# Task_2021-06-01.net
KiCad netlist of a schematic drawn in EasyEDA
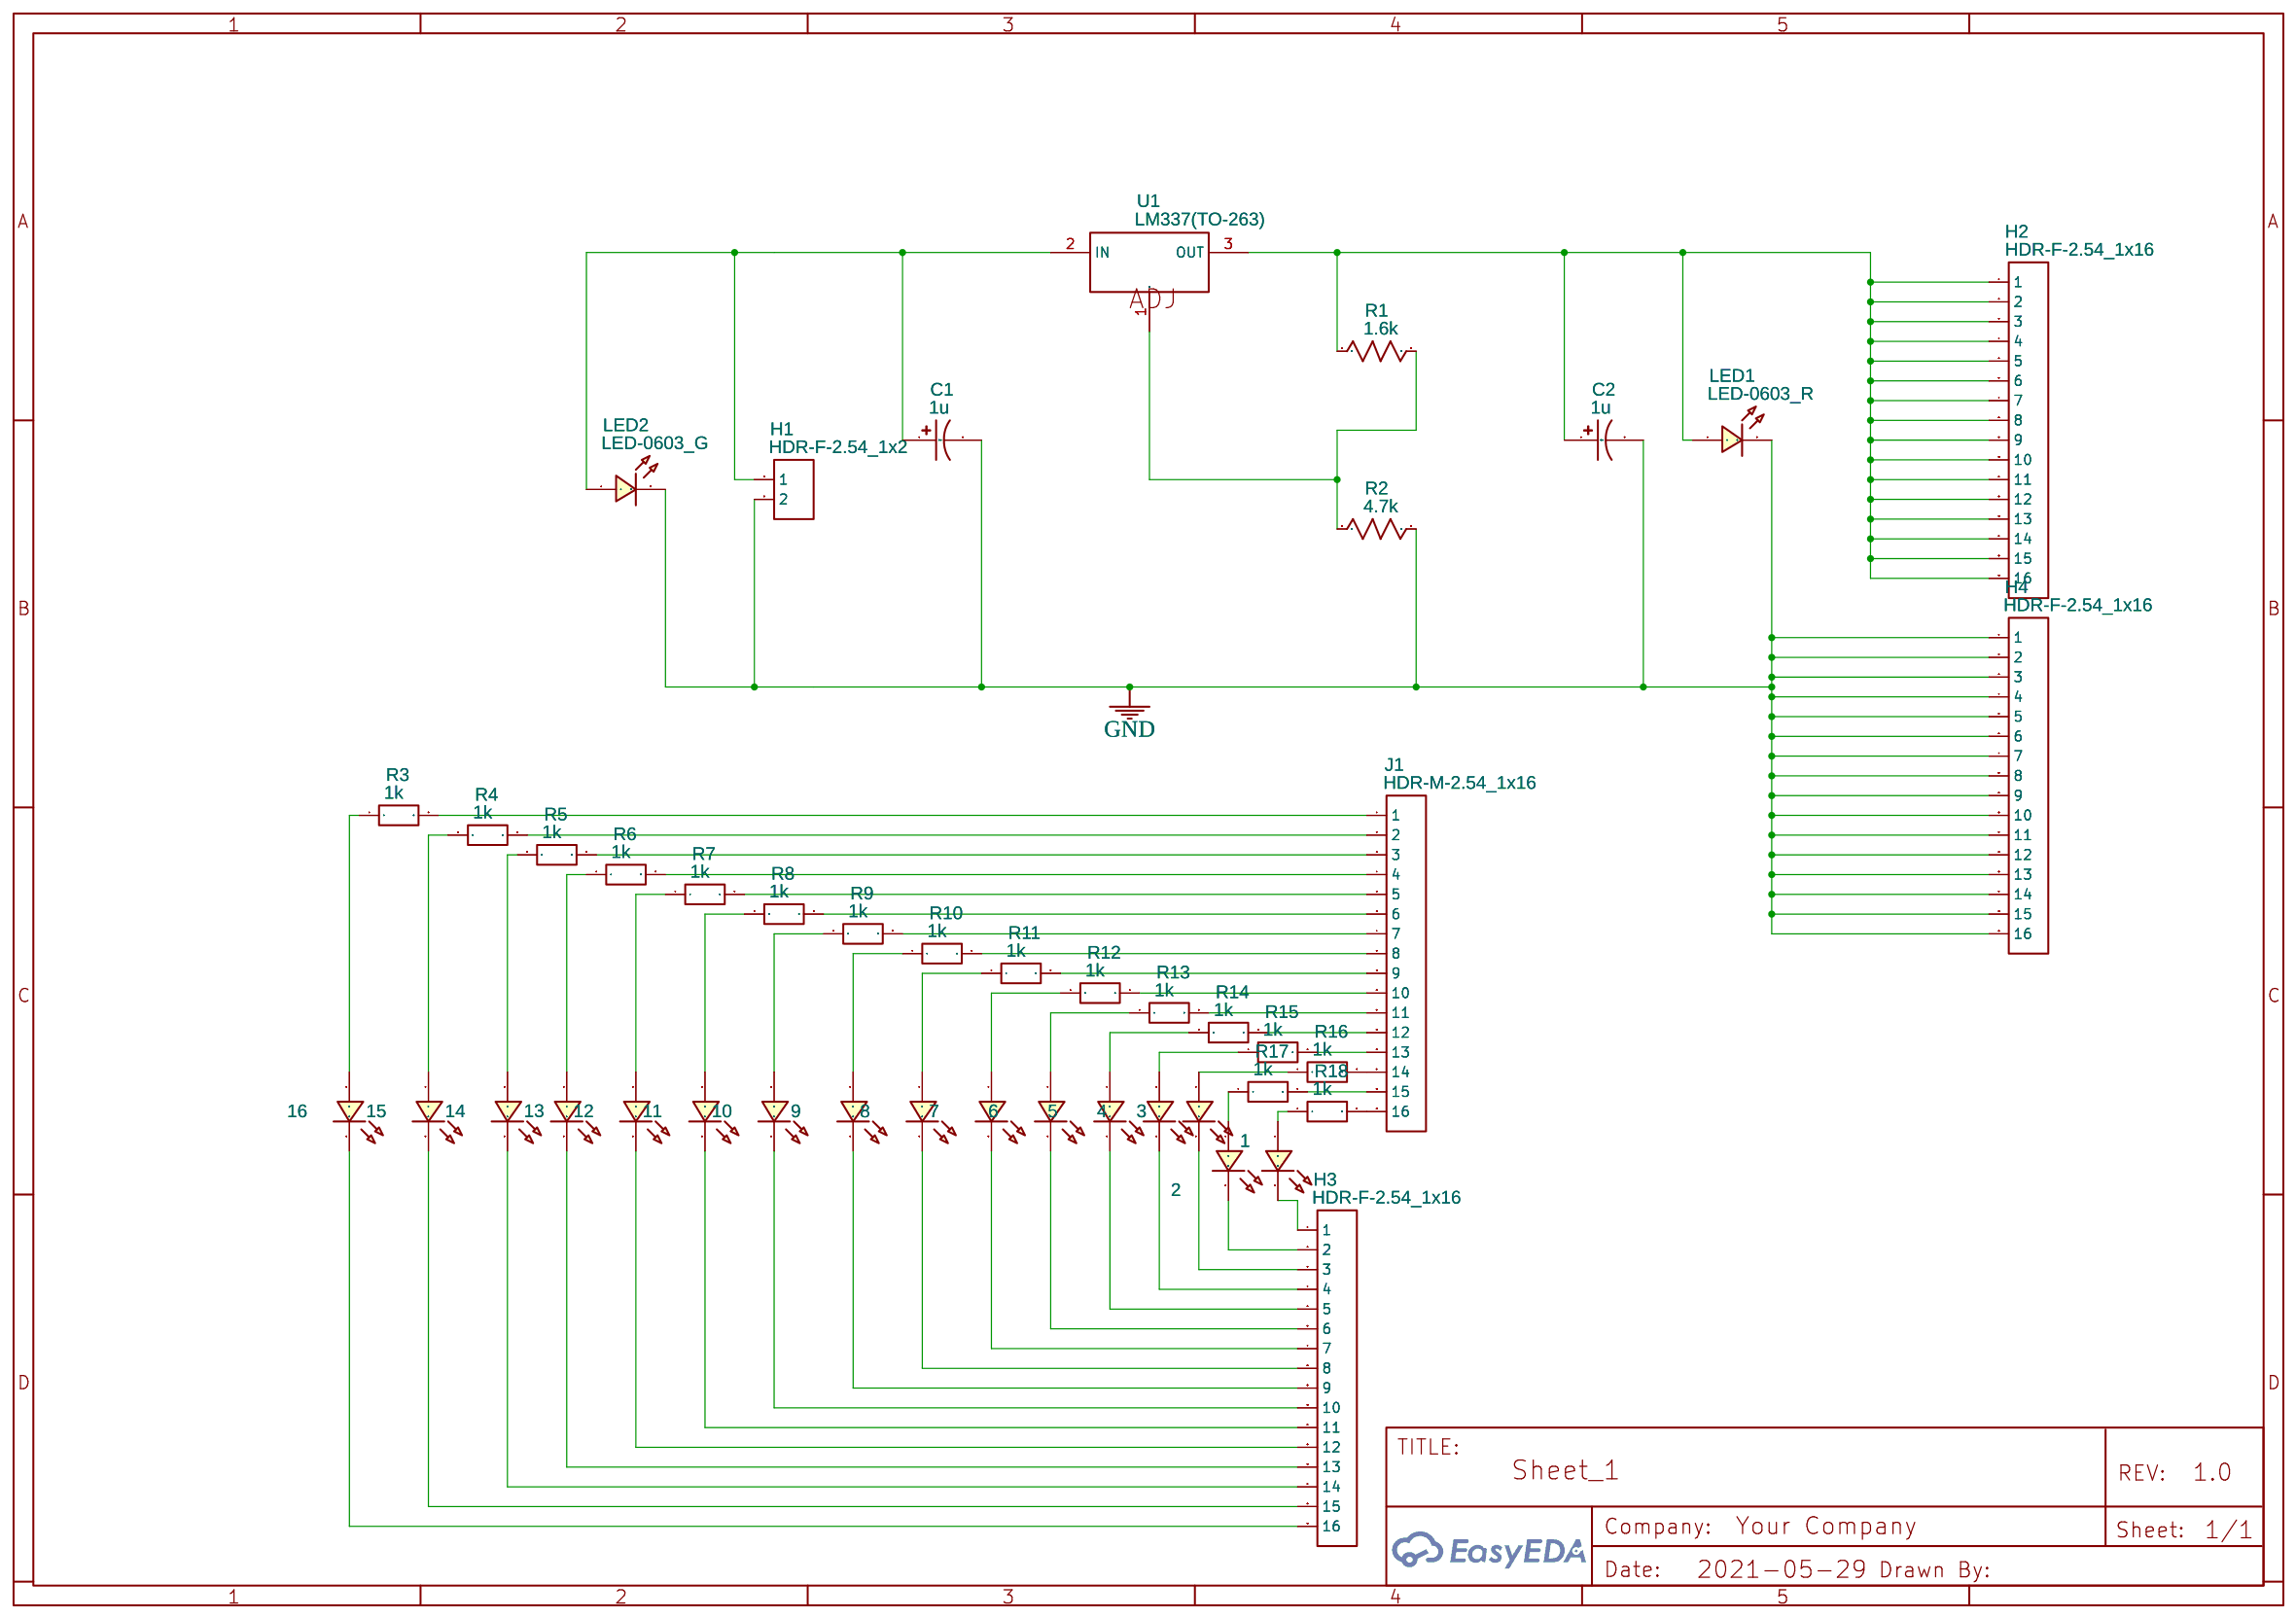
[diagram p0: schematic sheet]

(export (version "E")
  (design (tool "Eeschema 10.0.6"))
  (components
    (comp (ref "1")
      (value "LED-TH-3mm_B")
      (fields
        (field (name "BOM_Manufacturer Part") "204-10SUBC/S400-A4")
        (field (name "BOM_Supplier Part") "C86881")
      )
      (libsource (lib "") (part "LED-TH-3mm_B"))
    )
    (comp (ref "2")
      (value "LED-TH-3mm_B")
      (fields
        (field (name "BOM_Manufacturer Part") "204-10SUBC/S400-A4")
        (field (name "BOM_Supplier Part") "C86881")
      )
      (libsource (lib "") (part "LED-TH-3mm_B"))
    )
    (comp (ref "3")
      (value "LED-TH-3mm_B")
      (fields
        (field (name "BOM_Manufacturer Part") "204-10SUBC/S400-A4")
        (field (name "BOM_Supplier Part") "C86881")
      )
      (libsource (lib "") (part "LED-TH-3mm_B"))
    )
    (comp (ref "4")
      (value "LED-TH-3mm_B")
      (fields
        (field (name "BOM_Manufacturer Part") "204-10SUBC/S400-A4")
        (field (name "BOM_Supplier Part") "C86881")
      )
      (libsource (lib "") (part "LED-TH-3mm_B"))
    )
    (comp (ref "5")
      (value "LED-TH-3mm_B")
      (fields
        (field (name "BOM_Manufacturer Part") "204-10SUBC/S400-A4")
        (field (name "BOM_Supplier Part") "C86881")
      )
      (libsource (lib "") (part "LED-TH-3mm_B"))
    )
    (comp (ref "6")
      (value "LED-TH-3mm_B")
      (fields
        (field (name "BOM_Manufacturer Part") "204-10SUBC/S400-A4")
        (field (name "BOM_Supplier Part") "C86881")
      )
      (libsource (lib "") (part "LED-TH-3mm_B"))
    )
    (comp (ref "7")
      (value "LED-TH-3mm_B")
      (fields
        (field (name "BOM_Manufacturer Part") "204-10SUBC/S400-A4")
        (field (name "BOM_Supplier Part") "C86881")
      )
      (libsource (lib "") (part "LED-TH-3mm_B"))
    )
    (comp (ref "8")
      (value "LED-TH-3mm_B")
      (fields
        (field (name "BOM_Manufacturer Part") "204-10SUBC/S400-A4")
        (field (name "BOM_Supplier Part") "C86881")
      )
      (libsource (lib "") (part "LED-TH-3mm_B"))
    )
    (comp (ref "9")
      (value "LED-TH-3mm_B")
      (fields
        (field (name "BOM_Manufacturer Part") "204-10SUBC/S400-A4")
        (field (name "BOM_Supplier Part") "C86881")
      )
      (libsource (lib "") (part "LED-TH-3mm_B"))
    )
    (comp (ref "10")
      (value "LED-TH-3mm_B")
      (fields
        (field (name "BOM_Manufacturer Part") "204-10SUBC/S400-A4")
        (field (name "BOM_Supplier Part") "C86881")
      )
      (libsource (lib "") (part "LED-TH-3mm_B"))
    )
    (comp (ref "11")
      (value "LED-TH-3mm_B")
      (fields
        (field (name "BOM_Manufacturer Part") "204-10SUBC/S400-A4")
        (field (name "BOM_Supplier Part") "C86881")
      )
      (libsource (lib "") (part "LED-TH-3mm_B"))
    )
    (comp (ref "12")
      (value "LED-TH-3mm_B")
      (fields
        (field (name "BOM_Manufacturer Part") "204-10SUBC/S400-A4")
        (field (name "BOM_Supplier Part") "C86881")
      )
      (libsource (lib "") (part "LED-TH-3mm_B"))
    )
    (comp (ref "13")
      (value "LED-TH-3mm_B")
      (fields
        (field (name "BOM_Manufacturer Part") "204-10SUBC/S400-A4")
        (field (name "BOM_Supplier Part") "C86881")
      )
      (libsource (lib "") (part "LED-TH-3mm_B"))
    )
    (comp (ref "14")
      (value "LED-TH-3mm_B")
      (fields
        (field (name "BOM_Manufacturer Part") "204-10SUBC/S400-A4")
        (field (name "BOM_Supplier Part") "C86881")
      )
      (libsource (lib "") (part "LED-TH-3mm_B"))
    )
    (comp (ref "15")
      (value "LED-TH-3mm_B")
      (fields
        (field (name "BOM_Manufacturer Part") "204-10SUBC/S400-A4")
        (field (name "BOM_Supplier Part") "C86881")
      )
      (libsource (lib "") (part "LED-TH-3mm_B"))
    )
    (comp (ref "16")
      (value "LED-TH-3mm_B")
      (fields
        (field (name "BOM_Manufacturer Part") "204-10SUBC/S400-A4")
        (field (name "BOM_Supplier Part") "C86881")
      )
      (libsource (lib "") (part "LED-TH-3mm_B"))
    )
    (comp (ref "C1") (value "1u") (libsource (lib "") (part "C_Tan_SMD_A_US")))
    (comp (ref "C2") (value "1u") (libsource (lib "") (part "C_Tan_SMD_A_US")))
    (comp (ref "H1")
      (value "HDR-F-2.54_1x2")
      (fields (field (name "BOM_Supplier Part") "C49661"))
      (libsource (lib "") (part "HDR-F-2.54_1x2"))
    )
    (comp (ref "H2")
      (value "HDR-F-2.54_1x16")
      (fields (field (name "BOM_Supplier Part") "C66987"))
      (libsource (lib "") (part "HDR-F-2.54_1x16"))
    )
    (comp (ref "H3")
      (value "HDR-F-2.54_1x16")
      (fields (field (name "BOM_Supplier Part") "C66987"))
      (libsource (lib "") (part "HDR-F-2.54_1x16"))
    )
    (comp (ref "H4")
      (value "HDR-F-2.54_1x16")
      (fields (field (name "BOM_Supplier Part") "C66987"))
      (libsource (lib "") (part "HDR-F-2.54_1x16"))
    )
    (comp (ref "J1")
      (value "HDR-M-2.54_1x16")
      (fields (field (name "BOM_Supplier Part") "C50981"))
      (libsource (lib "") (part "HDR-M-2.54_1x16"))
    )
    (comp (ref "LED1")
      (value "LED-0603_R")
      (fields
        (field (name "BOM_Manufacturer Part") "19-217/R6C-AL1M2VY/3T")
        (field (name "BOM_Supplier Part") "C72044")
      )
      (libsource (lib "") (part "LED-0603_R"))
    )
    (comp (ref "LED2")
      (value "LED-0603_G")
      (fields
        (field (name "BOM_Manufacturer Part") "19-217/GHC-YR1S2/3T")
        (field (name "BOM_Supplier Part") "C72043")
      )
      (libsource (lib "") (part "LED-0603_G"))
    )
    (comp (ref "R1") (value "1.6k") (libsource (lib "") (part "R_0603_US")))
    (comp (ref "R2") (value "4.7k") (libsource (lib "") (part "R_0603_US")))
    (comp (ref "R3") (value "1k") (libsource (lib "") (part "R_0603_EU")))
    (comp (ref "R4") (value "1k") (libsource (lib "") (part "R_0603_EU")))
    (comp (ref "R5") (value "1k") (libsource (lib "") (part "R_0603_EU")))
    (comp (ref "R6") (value "1k") (libsource (lib "") (part "R_0603_EU")))
    (comp (ref "R7") (value "1k") (libsource (lib "") (part "R_0603_EU")))
    (comp (ref "R8") (value "1k") (libsource (lib "") (part "R_0603_EU")))
    (comp (ref "R9") (value "1k") (libsource (lib "") (part "R_0603_EU")))
    (comp (ref "R10") (value "1k") (libsource (lib "") (part "R_0603_EU")))
    (comp (ref "R11") (value "1k") (libsource (lib "") (part "R_0603_EU")))
    (comp (ref "R12") (value "1k") (libsource (lib "") (part "R_0603_EU")))
    (comp (ref "R13") (value "1k") (libsource (lib "") (part "R_0603_EU")))
    (comp (ref "R14") (value "1k") (libsource (lib "") (part "R_0603_EU")))
    (comp (ref "R15") (value "1k") (libsource (lib "") (part "R_0603_EU")))
    (comp (ref "R16") (value "1k") (libsource (lib "") (part "R_0603_EU")))
    (comp (ref "R17") (value "1k") (libsource (lib "") (part "R_0603_EU")))
    (comp (ref "R18") (value "1k") (libsource (lib "") (part "R_0603_EU")))
    (comp (ref "U1")
      (value "LM337(TO-263)")
      (fields (field (name "BOM_Manufacturer Part") "LM337D2TG") (field (name "BOM_Supplier Part") "C146782"))
      (libsource (lib "") (part "LM337(TO-263)"))
    )
  )
  (nets
    (net (code "1") (name "GND") (class "Default")
      (node (ref "C1") (pin "2") (pinfunction "2_2") (pintype "unspecified"))
      (node (ref "C2") (pin "2") (pinfunction "2_2") (pintype "unspecified"))
      (node (ref "H1") (pin "2") (pinfunction "2_2") (pintype "input"))
      (node (ref "H4") (pin "1") (pinfunction "1_1") (pintype "unspecified"))
      (node (ref "H4") (pin "10") (pinfunction "10_10") (pintype "unspecified"))
      (node (ref "H4") (pin "11") (pinfunction "11_11") (pintype "unspecified"))
      (node (ref "H4") (pin "12") (pinfunction "12_12") (pintype "unspecified"))
      (node (ref "H4") (pin "13") (pinfunction "13_13") (pintype "unspecified"))
      (node (ref "H4") (pin "14") (pinfunction "14_14") (pintype "unspecified"))
      (node (ref "H4") (pin "15") (pinfunction "15_15") (pintype "unspecified"))
      (node (ref "H4") (pin "16") (pinfunction "16_16") (pintype "unspecified"))
      (node (ref "H4") (pin "2") (pinfunction "2_2") (pintype "unspecified"))
      (node (ref "H4") (pin "3") (pinfunction "3_3") (pintype "unspecified"))
      (node (ref "H4") (pin "4") (pinfunction "4_4") (pintype "unspecified"))
      (node (ref "H4") (pin "5") (pinfunction "5_5") (pintype "unspecified"))
      (node (ref "H4") (pin "6") (pinfunction "6_6") (pintype "unspecified"))
      (node (ref "H4") (pin "7") (pinfunction "7_7") (pintype "unspecified"))
      (node (ref "H4") (pin "8") (pinfunction "8_8") (pintype "unspecified"))
      (node (ref "H4") (pin "9") (pinfunction "9_9") (pintype "unspecified"))
      (node (ref "LED1") (pin "2") (pinfunction "2_2") (pintype "unspecified"))
      (node (ref "LED2") (pin "2") (pinfunction "2_2") (pintype "unspecified"))
      (node (ref "R2") (pin "2") (pinfunction "2_2") (pintype "unspecified"))
    )
    (net (code "2") (name "Net-(1-Pad1)") (class "Default")
      (node (ref "1") (pin "1") (pinfunction "1_1") (pintype "unspecified"))
      (node (ref "R18") (pin "1") (pinfunction "1_1") (pintype "unspecified"))
    )
    (net (code "3") (name "Net-(1-Pad2)") (class "Default")
      (node (ref "1") (pin "2") (pinfunction "2_2") (pintype "unspecified"))
      (node (ref "H3") (pin "1") (pinfunction "1_1") (pintype "unspecified"))
    )
    (net (code "4") (name "Net-(2-Pad1)") (class "Default")
      (node (ref "2") (pin "1") (pinfunction "1_1") (pintype "unspecified"))
      (node (ref "R17") (pin "1") (pinfunction "1_1") (pintype "unspecified"))
    )
    (net (code "5") (name "Net-(2-Pad2)") (class "Default")
      (node (ref "2") (pin "2") (pinfunction "2_2") (pintype "unspecified"))
      (node (ref "H3") (pin "2") (pinfunction "2_2") (pintype "unspecified"))
    )
    (net (code "6") (name "Net-(3-Pad1)") (class "Default")
      (node (ref "3") (pin "1") (pinfunction "1_1") (pintype "unspecified"))
      (node (ref "R16") (pin "1") (pinfunction "1_1") (pintype "unspecified"))
    )
    (net (code "7") (name "Net-(3-Pad2)") (class "Default")
      (node (ref "3") (pin "2") (pinfunction "2_2") (pintype "unspecified"))
      (node (ref "H3") (pin "3") (pinfunction "3_3") (pintype "unspecified"))
    )
    (net (code "8") (name "Net-(4-Pad1)") (class "Default")
      (node (ref "4") (pin "1") (pinfunction "1_1") (pintype "unspecified"))
      (node (ref "R15") (pin "1") (pinfunction "1_1") (pintype "unspecified"))
    )
    (net (code "9") (name "Net-(4-Pad2)") (class "Default")
      (node (ref "4") (pin "2") (pinfunction "2_2") (pintype "unspecified"))
      (node (ref "H3") (pin "4") (pinfunction "4_4") (pintype "unspecified"))
    )
    (net (code "10") (name "Net-(5-Pad1)") (class "Default")
      (node (ref "5") (pin "1") (pinfunction "1_1") (pintype "unspecified"))
      (node (ref "R14") (pin "1") (pinfunction "1_1") (pintype "unspecified"))
    )
    (net (code "11") (name "Net-(5-Pad2)") (class "Default")
      (node (ref "5") (pin "2") (pinfunction "2_2") (pintype "unspecified"))
      (node (ref "H3") (pin "5") (pinfunction "5_5") (pintype "unspecified"))
    )
    (net (code "12") (name "Net-(6-Pad1)") (class "Default")
      (node (ref "6") (pin "1") (pinfunction "1_1") (pintype "unspecified"))
      (node (ref "R13") (pin "1") (pinfunction "1_1") (pintype "unspecified"))
    )
    (net (code "13") (name "Net-(6-Pad2)") (class "Default")
      (node (ref "6") (pin "2") (pinfunction "2_2") (pintype "unspecified"))
      (node (ref "H3") (pin "6") (pinfunction "6_6") (pintype "unspecified"))
    )
    (net (code "14") (name "Net-(7-Pad1)") (class "Default")
      (node (ref "7") (pin "1") (pinfunction "1_1") (pintype "unspecified"))
      (node (ref "R12") (pin "1") (pinfunction "1_1") (pintype "unspecified"))
    )
    (net (code "15") (name "Net-(7-Pad2)") (class "Default")
      (node (ref "7") (pin "2") (pinfunction "2_2") (pintype "unspecified"))
      (node (ref "H3") (pin "7") (pinfunction "7_7") (pintype "unspecified"))
    )
    (net (code "16") (name "Net-(8-Pad1)") (class "Default")
      (node (ref "8") (pin "1") (pinfunction "1_1") (pintype "unspecified"))
      (node (ref "R11") (pin "1") (pinfunction "1_1") (pintype "unspecified"))
    )
    (net (code "17") (name "Net-(8-Pad2)") (class "Default")
      (node (ref "8") (pin "2") (pinfunction "2_2") (pintype "unspecified"))
      (node (ref "H3") (pin "8") (pinfunction "8_8") (pintype "unspecified"))
    )
    (net (code "18") (name "Net-(9-Pad1)") (class "Default")
      (node (ref "9") (pin "1") (pinfunction "1_1") (pintype "unspecified"))
      (node (ref "R10") (pin "1") (pinfunction "1_1") (pintype "unspecified"))
    )
    (net (code "19") (name "Net-(9-Pad2)") (class "Default")
      (node (ref "9") (pin "2") (pinfunction "2_2") (pintype "unspecified"))
      (node (ref "H3") (pin "9") (pinfunction "9_9") (pintype "unspecified"))
    )
    (net (code "20") (name "Net-(10-Pad1)") (class "Default")
      (node (ref "10") (pin "1") (pinfunction "1_1") (pintype "unspecified"))
      (node (ref "R9") (pin "1") (pinfunction "1_1") (pintype "unspecified"))
    )
    (net (code "21") (name "Net-(10-Pad2)") (class "Default")
      (node (ref "10") (pin "2") (pinfunction "2_2") (pintype "unspecified"))
      (node (ref "H3") (pin "10") (pinfunction "10_10") (pintype "unspecified"))
    )
    (net (code "22") (name "Net-(11-Pad1)") (class "Default")
      (node (ref "11") (pin "1") (pinfunction "1_1") (pintype "unspecified"))
      (node (ref "R8") (pin "1") (pinfunction "1_1") (pintype "unspecified"))
    )
    (net (code "23") (name "Net-(11-Pad2)") (class "Default")
      (node (ref "11") (pin "2") (pinfunction "2_2") (pintype "unspecified"))
      (node (ref "H3") (pin "11") (pinfunction "11_11") (pintype "unspecified"))
    )
    (net (code "24") (name "Net-(12-Pad1)") (class "Default")
      (node (ref "12") (pin "1") (pinfunction "1_1") (pintype "unspecified"))
      (node (ref "R7") (pin "1") (pinfunction "1_1") (pintype "unspecified"))
    )
    (net (code "25") (name "Net-(12-Pad2)") (class "Default")
      (node (ref "12") (pin "2") (pinfunction "2_2") (pintype "unspecified"))
      (node (ref "H3") (pin "12") (pinfunction "12_12") (pintype "unspecified"))
    )
    (net (code "26") (name "Net-(13-Pad1)") (class "Default")
      (node (ref "13") (pin "1") (pinfunction "1_1") (pintype "unspecified"))
      (node (ref "R6") (pin "1") (pinfunction "1_1") (pintype "unspecified"))
    )
    (net (code "27") (name "Net-(13-Pad2)") (class "Default")
      (node (ref "13") (pin "2") (pinfunction "2_2") (pintype "unspecified"))
      (node (ref "H3") (pin "13") (pinfunction "13_13") (pintype "unspecified"))
    )
    (net (code "28") (name "Net-(14-Pad1)") (class "Default")
      (node (ref "14") (pin "1") (pinfunction "1_1") (pintype "unspecified"))
      (node (ref "R5") (pin "1") (pinfunction "1_1") (pintype "unspecified"))
    )
    (net (code "29") (name "Net-(14-Pad2)") (class "Default")
      (node (ref "14") (pin "2") (pinfunction "2_2") (pintype "unspecified"))
      (node (ref "H3") (pin "14") (pinfunction "14_14") (pintype "unspecified"))
    )
    (net (code "30") (name "Net-(15-Pad1)") (class "Default")
      (node (ref "15") (pin "1") (pinfunction "1_1") (pintype "unspecified"))
      (node (ref "R4") (pin "1") (pinfunction "1_1") (pintype "unspecified"))
    )
    (net (code "31") (name "Net-(15-Pad2)") (class "Default")
      (node (ref "15") (pin "2") (pinfunction "2_2") (pintype "unspecified"))
      (node (ref "H3") (pin "15") (pinfunction "15_15") (pintype "unspecified"))
    )
    (net (code "32") (name "Net-(16-Pad1)") (class "Default")
      (node (ref "16") (pin "1") (pinfunction "1_1") (pintype "unspecified"))
      (node (ref "R3") (pin "1") (pinfunction "1_1") (pintype "unspecified"))
    )
    (net (code "33") (name "Net-(16-Pad2)") (class "Default")
      (node (ref "16") (pin "2") (pinfunction "2_2") (pintype "unspecified"))
      (node (ref "H3") (pin "16") (pinfunction "16_16") (pintype "unspecified"))
    )
    (net (code "34") (name "Net-(J1-Pad1)") (class "Default")
      (node (ref "J1") (pin "1") (pinfunction "1_1") (pintype "unspecified"))
      (node (ref "R3") (pin "2") (pinfunction "2_2") (pintype "unspecified"))
    )
    (net (code "35") (name "Net-(J1-Pad2)") (class "Default")
      (node (ref "J1") (pin "2") (pinfunction "2_2") (pintype "unspecified"))
      (node (ref "R4") (pin "2") (pinfunction "2_2") (pintype "unspecified"))
    )
    (net (code "36") (name "Net-(J1-Pad3)") (class "Default")
      (node (ref "J1") (pin "3") (pinfunction "3_3") (pintype "unspecified"))
      (node (ref "R5") (pin "2") (pinfunction "2_2") (pintype "unspecified"))
    )
    (net (code "37") (name "Net-(J1-Pad4)") (class "Default")
      (node (ref "J1") (pin "4") (pinfunction "4_4") (pintype "unspecified"))
      (node (ref "R6") (pin "2") (pinfunction "2_2") (pintype "unspecified"))
    )
    (net (code "38") (name "Net-(J1-Pad5)") (class "Default")
      (node (ref "J1") (pin "5") (pinfunction "5_5") (pintype "unspecified"))
      (node (ref "R7") (pin "2") (pinfunction "2_2") (pintype "unspecified"))
    )
    (net (code "39") (name "Net-(J1-Pad6)") (class "Default")
      (node (ref "J1") (pin "6") (pinfunction "6_6") (pintype "unspecified"))
      (node (ref "R8") (pin "2") (pinfunction "2_2") (pintype "unspecified"))
    )
    (net (code "40") (name "Net-(J1-Pad7)") (class "Default")
      (node (ref "J1") (pin "7") (pinfunction "7_7") (pintype "unspecified"))
      (node (ref "R9") (pin "2") (pinfunction "2_2") (pintype "unspecified"))
    )
    (net (code "41") (name "Net-(J1-Pad8)") (class "Default")
      (node (ref "J1") (pin "8") (pinfunction "8_8") (pintype "unspecified"))
      (node (ref "R10") (pin "2") (pinfunction "2_2") (pintype "unspecified"))
    )
    (net (code "42") (name "Net-(J1-Pad9)") (class "Default")
      (node (ref "J1") (pin "9") (pinfunction "9_9") (pintype "unspecified"))
      (node (ref "R11") (pin "2") (pinfunction "2_2") (pintype "unspecified"))
    )
    (net (code "43") (name "Net-(J1-Pad10)") (class "Default")
      (node (ref "J1") (pin "10") (pinfunction "10_10") (pintype "unspecified"))
      (node (ref "R12") (pin "2") (pinfunction "2_2") (pintype "unspecified"))
    )
    (net (code "44") (name "Net-(J1-Pad11)") (class "Default")
      (node (ref "J1") (pin "11") (pinfunction "11_11") (pintype "unspecified"))
      (node (ref "R13") (pin "2") (pinfunction "2_2") (pintype "unspecified"))
    )
    (net (code "45") (name "Net-(J1-Pad12)") (class "Default")
      (node (ref "J1") (pin "12") (pinfunction "12_12") (pintype "unspecified"))
      (node (ref "R14") (pin "2") (pinfunction "2_2") (pintype "unspecified"))
    )
    (net (code "46") (name "Net-(J1-Pad13)") (class "Default")
      (node (ref "J1") (pin "13") (pinfunction "13_13") (pintype "unspecified"))
      (node (ref "R15") (pin "2") (pinfunction "2_2") (pintype "unspecified"))
    )
    (net (code "47") (name "Net-(J1-Pad14)") (class "Default")
      (node (ref "J1") (pin "14") (pinfunction "14_14") (pintype "unspecified"))
      (node (ref "R16") (pin "2") (pinfunction "2_2") (pintype "unspecified"))
    )
    (net (code "48") (name "Net-(J1-Pad15)") (class "Default")
      (node (ref "J1") (pin "15") (pinfunction "15_15") (pintype "unspecified"))
      (node (ref "R17") (pin "2") (pinfunction "2_2") (pintype "unspecified"))
    )
    (net (code "49") (name "Net-(J1-Pad16)") (class "Default")
      (node (ref "J1") (pin "16") (pinfunction "16_16") (pintype "unspecified"))
      (node (ref "R18") (pin "2") (pinfunction "2_2") (pintype "unspecified"))
    )
    (net (code "50") (name "Net-(U1-ADJ)") (class "Default")
      (node (ref "R1") (pin "2") (pinfunction "2_2") (pintype "unspecified"))
      (node (ref "R2") (pin "1") (pinfunction "1_1") (pintype "unspecified"))
      (node (ref "U1") (pin "1") (pinfunction "ADJ_1") (pintype "passive"))
    )
    (net (code "51") (name "Net-(U1-IN)") (class "Default")
      (node (ref "C1") (pin "1") (pinfunction "1_1") (pintype "unspecified"))
      (node (ref "H1") (pin "1") (pinfunction "1_1") (pintype "input"))
      (node (ref "LED2") (pin "1") (pinfunction "1_1") (pintype "unspecified"))
      (node (ref "U1") (pin "2") (pinfunction "IN_2") (pintype "passive"))
    )
    (net (code "52") (name "Net-(U1-OUT)") (class "Default")
      (node (ref "C2") (pin "1") (pinfunction "1_1") (pintype "unspecified"))
      (node (ref "H2") (pin "1") (pinfunction "1_1") (pintype "unspecified"))
      (node (ref "H2") (pin "10") (pinfunction "10_10") (pintype "unspecified"))
      (node (ref "H2") (pin "11") (pinfunction "11_11") (pintype "unspecified"))
      (node (ref "H2") (pin "12") (pinfunction "12_12") (pintype "unspecified"))
      (node (ref "H2") (pin "13") (pinfunction "13_13") (pintype "unspecified"))
      (node (ref "H2") (pin "14") (pinfunction "14_14") (pintype "unspecified"))
      (node (ref "H2") (pin "15") (pinfunction "15_15") (pintype "unspecified"))
      (node (ref "H2") (pin "16") (pinfunction "16_16") (pintype "unspecified"))
      (node (ref "H2") (pin "2") (pinfunction "2_2") (pintype "unspecified"))
      (node (ref "H2") (pin "3") (pinfunction "3_3") (pintype "unspecified"))
      (node (ref "H2") (pin "4") (pinfunction "4_4") (pintype "unspecified"))
      (node (ref "H2") (pin "5") (pinfunction "5_5") (pintype "unspecified"))
      (node (ref "H2") (pin "6") (pinfunction "6_6") (pintype "unspecified"))
      (node (ref "H2") (pin "7") (pinfunction "7_7") (pintype "unspecified"))
      (node (ref "H2") (pin "8") (pinfunction "8_8") (pintype "unspecified"))
      (node (ref "H2") (pin "9") (pinfunction "9_9") (pintype "unspecified"))
      (node (ref "LED1") (pin "1") (pinfunction "1_1") (pintype "unspecified"))
      (node (ref "R1") (pin "1") (pinfunction "1_1") (pintype "unspecified"))
      (node (ref "U1") (pin "3") (pinfunction "OUT_3") (pintype "passive"))
    )
  )
)
